# top_level.net
KiCad netlist of a schematic drawn in Altium Designer
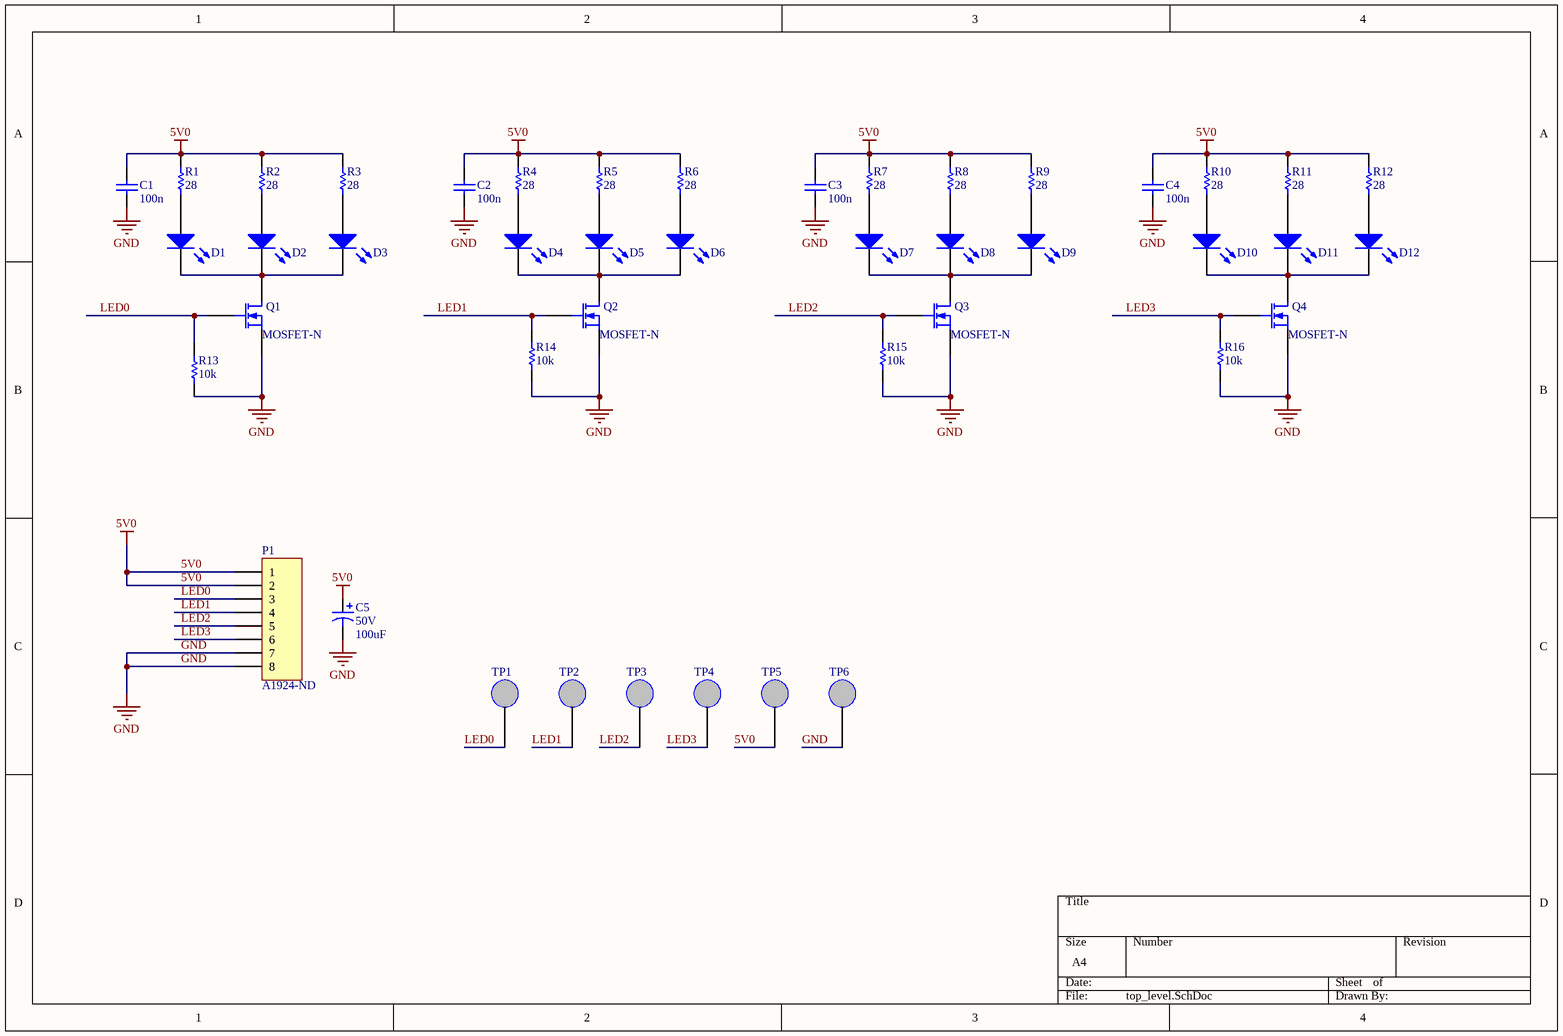
[diagram p0: top_level.SchDoc]

(export (version "E")
  (design (tool "Eeschema 10.0.6"))
  (components
    (comp (ref "C1")
      (value "100n")
      (footprint "CS-0603")
      (fields
        (field (name "TOLERANCE") "10%")
        (field (name "VOLTAGE") "16V")
        (field (name "Comment") "CS - CAPACITOR")
      )
      (libsource (lib "CHINOOK_LIBRARY") (part "CS - CAPACITOR"))
    )
    (comp (ref "C2")
      (value "100n")
      (footprint "CS-0603")
      (fields
        (field (name "TOLERANCE") "10%")
        (field (name "VOLTAGE") "16V")
        (field (name "Comment") "CS - CAPACITOR")
      )
      (libsource (lib "CHINOOK_LIBRARY") (part "CS - CAPACITOR"))
    )
    (comp (ref "C3")
      (value "100n")
      (footprint "CS-0603")
      (fields
        (field (name "TOLERANCE") "10%")
        (field (name "VOLTAGE") "16V")
        (field (name "Comment") "CS - CAPACITOR")
      )
      (libsource (lib "CHINOOK_LIBRARY") (part "CS - CAPACITOR"))
    )
    (comp (ref "C4")
      (value "100n")
      (footprint "CS-0603")
      (fields
        (field (name "TOLERANCE") "10%")
        (field (name "VOLTAGE") "16V")
        (field (name "Comment") "CS - CAPACITOR")
      )
      (libsource (lib "CHINOOK_LIBRARY") (part "CS - CAPACITOR"))
    )
    (comp (ref "C5")
      (value "100uF")
      (footprint "CT-CAP-ALUM-8X14")
      (fields
        (field (name "TOLERANCE") "10%")
        (field (name "VOLTAGE") "50V")
        (field (name "Comment") "CT - CAPACITOR ELECTROLYTIC")
      )
      (libsource (lib "CHINOOK_LIBRARY") (part "CT - CAPACITOR ELECTROLYTIC"))
    )
    (comp (ref "D1")
      (value "LED - NORMAL LED")
      (footprint "LED-1")
      (libsource (lib "CHINOOK_LIBRARY") (part "LED - NORMAL LED"))
    )
    (comp (ref "D2")
      (value "LED - NORMAL LED")
      (footprint "LED-1")
      (libsource (lib "CHINOOK_LIBRARY") (part "LED - NORMAL LED"))
    )
    (comp (ref "D3")
      (value "LED - NORMAL LED")
      (footprint "LED-1")
      (libsource (lib "CHINOOK_LIBRARY") (part "LED - NORMAL LED"))
    )
    (comp (ref "D4")
      (value "LED - NORMAL LED")
      (footprint "LED-1")
      (libsource (lib "CHINOOK_LIBRARY") (part "LED - NORMAL LED"))
    )
    (comp (ref "D5")
      (value "LED - NORMAL LED")
      (footprint "LED-1")
      (libsource (lib "CHINOOK_LIBRARY") (part "LED - NORMAL LED"))
    )
    (comp (ref "D6")
      (value "LED - NORMAL LED")
      (footprint "LED-1")
      (libsource (lib "CHINOOK_LIBRARY") (part "LED - NORMAL LED"))
    )
    (comp (ref "D7")
      (value "LED - NORMAL LED")
      (footprint "LED-1")
      (libsource (lib "CHINOOK_LIBRARY") (part "LED - NORMAL LED"))
    )
    (comp (ref "D8")
      (value "LED - NORMAL LED")
      (footprint "LED-1")
      (libsource (lib "CHINOOK_LIBRARY") (part "LED - NORMAL LED"))
    )
    (comp (ref "D9")
      (value "LED - NORMAL LED")
      (footprint "LED-1")
      (libsource (lib "CHINOOK_LIBRARY") (part "LED - NORMAL LED"))
    )
    (comp (ref "D10")
      (value "LED - NORMAL LED")
      (footprint "LED-1")
      (libsource (lib "CHINOOK_LIBRARY") (part "LED - NORMAL LED"))
    )
    (comp (ref "D11")
      (value "LED - NORMAL LED")
      (footprint "LED-1")
      (libsource (lib "CHINOOK_LIBRARY") (part "LED - NORMAL LED"))
    )
    (comp (ref "D12")
      (value "LED - NORMAL LED")
      (footprint "LED-1")
      (libsource (lib "CHINOOK_LIBRARY") (part "LED - NORMAL LED"))
    )
    (comp (ref "P1")
      (value "CON - HEADER 1X8")
      (footprint "CON-HEADER-1X8")
      (description "100mil header 1 row 6 pins")
      (fields (field (name "SUPPLIER PART NUMBER 1") "A1924-ND"))
      (libsource (lib "CHINOOK_LIBRARY") (part "CON - HEADER 1X8"))
    )
    (comp (ref "Q1")
      (value "MOSFET-N")
      (footprint "TO-220AB")
      (description "N-Channel MOSFET")
      (fields (field (name "PUBLISHER") "Altium Limited"))
      (libsource (lib "Miscellaneous Devices") (part "MOSFET-N"))
    )
    (comp (ref "Q2")
      (value "MOSFET-N")
      (footprint "TO-220AB")
      (description "N-Channel MOSFET")
      (fields (field (name "PUBLISHER") "Altium Limited"))
      (libsource (lib "Miscellaneous Devices") (part "MOSFET-N"))
    )
    (comp (ref "Q3")
      (value "MOSFET-N")
      (footprint "TO-220AB")
      (description "N-Channel MOSFET")
      (fields (field (name "PUBLISHER") "Altium Limited"))
      (libsource (lib "Miscellaneous Devices") (part "MOSFET-N"))
    )
    (comp (ref "Q4")
      (value "MOSFET-N")
      (footprint "TO-220AB")
      (description "N-Channel MOSFET")
      (fields (field (name "PUBLISHER") "Altium Limited"))
      (libsource (lib "Miscellaneous Devices") (part "MOSFET-N"))
    )
    (comp (ref "R1")
      (value "28")
      (footprint "RS-1210")
      (fields
        (field (name "TOLERANCE") "RES TOL")
        (field (name "POWER") "RES POWER")
        (field (name "Comment") "RS - RESISTOR")
      )
      (libsource (lib "CHINOOK_LIBRARY") (part "RS - RESISTOR"))
    )
    (comp (ref "R2")
      (value "28")
      (footprint "RS-1210")
      (fields
        (field (name "TOLERANCE") "RES TOL")
        (field (name "POWER") "RES POWER")
        (field (name "Comment") "RS - RESISTOR")
      )
      (libsource (lib "CHINOOK_LIBRARY") (part "RS - RESISTOR"))
    )
    (comp (ref "R3")
      (value "28")
      (footprint "RS-1210")
      (fields
        (field (name "TOLERANCE") "RES TOL")
        (field (name "POWER") "RES POWER")
        (field (name "Comment") "RS - RESISTOR")
      )
      (libsource (lib "CHINOOK_LIBRARY") (part "RS - RESISTOR"))
    )
    (comp (ref "R4")
      (value "28")
      (footprint "RS-1210")
      (fields
        (field (name "TOLERANCE") "RES TOL")
        (field (name "POWER") "RES POWER")
        (field (name "Comment") "RS - RESISTOR")
      )
      (libsource (lib "CHINOOK_LIBRARY") (part "RS - RESISTOR"))
    )
    (comp (ref "R5")
      (value "28")
      (footprint "RS-1210")
      (fields
        (field (name "TOLERANCE") "RES TOL")
        (field (name "POWER") "RES POWER")
        (field (name "Comment") "RS - RESISTOR")
      )
      (libsource (lib "CHINOOK_LIBRARY") (part "RS - RESISTOR"))
    )
    (comp (ref "R6")
      (value "28")
      (footprint "RS-1210")
      (fields
        (field (name "TOLERANCE") "RES TOL")
        (field (name "POWER") "RES POWER")
        (field (name "Comment") "RS - RESISTOR")
      )
      (libsource (lib "CHINOOK_LIBRARY") (part "RS - RESISTOR"))
    )
    (comp (ref "R7")
      (value "28")
      (footprint "RS-1210")
      (fields
        (field (name "TOLERANCE") "RES TOL")
        (field (name "POWER") "RES POWER")
        (field (name "Comment") "RS - RESISTOR")
      )
      (libsource (lib "CHINOOK_LIBRARY") (part "RS - RESISTOR"))
    )
    (comp (ref "R8")
      (value "28")
      (footprint "RS-1210")
      (fields
        (field (name "TOLERANCE") "RES TOL")
        (field (name "POWER") "RES POWER")
        (field (name "Comment") "RS - RESISTOR")
      )
      (libsource (lib "CHINOOK_LIBRARY") (part "RS - RESISTOR"))
    )
    (comp (ref "R9")
      (value "28")
      (footprint "RS-1210")
      (fields
        (field (name "TOLERANCE") "RES TOL")
        (field (name "POWER") "RES POWER")
        (field (name "Comment") "RS - RESISTOR")
      )
      (libsource (lib "CHINOOK_LIBRARY") (part "RS - RESISTOR"))
    )
    (comp (ref "R10")
      (value "28")
      (footprint "RS-1210")
      (fields
        (field (name "TOLERANCE") "RES TOL")
        (field (name "POWER") "RES POWER")
        (field (name "Comment") "RS - RESISTOR")
      )
      (libsource (lib "CHINOOK_LIBRARY") (part "RS - RESISTOR"))
    )
    (comp (ref "R11")
      (value "28")
      (footprint "RS-1210")
      (fields
        (field (name "TOLERANCE") "RES TOL")
        (field (name "POWER") "RES POWER")
        (field (name "Comment") "RS - RESISTOR")
      )
      (libsource (lib "CHINOOK_LIBRARY") (part "RS - RESISTOR"))
    )
    (comp (ref "R12")
      (value "28")
      (footprint "RS-1210")
      (fields
        (field (name "TOLERANCE") "RES TOL")
        (field (name "POWER") "RES POWER")
        (field (name "Comment") "RS - RESISTOR")
      )
      (libsource (lib "CHINOOK_LIBRARY") (part "RS - RESISTOR"))
    )
    (comp (ref "R13")
      (value "10k")
      (footprint "RS-0603")
      (fields
        (field (name "TOLERANCE") "RES TOL")
        (field (name "POWER") "RES POWER")
        (field (name "Comment") "RS - RESISTOR")
      )
      (libsource (lib "CHINOOK_LIBRARY") (part "RS - RESISTOR"))
    )
    (comp (ref "R14")
      (value "10k")
      (footprint "RS-0603")
      (fields
        (field (name "TOLERANCE") "RES TOL")
        (field (name "POWER") "RES POWER")
        (field (name "Comment") "RS - RESISTOR")
      )
      (libsource (lib "CHINOOK_LIBRARY") (part "RS - RESISTOR"))
    )
    (comp (ref "R15")
      (value "10k")
      (footprint "RS-0603")
      (fields
        (field (name "TOLERANCE") "RES TOL")
        (field (name "POWER") "RES POWER")
        (field (name "Comment") "RS - RESISTOR")
      )
      (libsource (lib "CHINOOK_LIBRARY") (part "RS - RESISTOR"))
    )
    (comp (ref "R16")
      (value "10k")
      (footprint "RS-0603")
      (fields
        (field (name "TOLERANCE") "RES TOL")
        (field (name "POWER") "RES POWER")
        (field (name "Comment") "RS - RESISTOR")
      )
      (libsource (lib "CHINOOK_LIBRARY") (part "RS - RESISTOR"))
    )
    (comp (ref "TP1")
      (value "5003K")
      (footprint "TP - VERTICAL")
      (libsource (lib "CHINOOK_LIBRARY") (part "TP - Test point vertical"))
    )
    (comp (ref "TP2")
      (value "5003K")
      (footprint "TP - VERTICAL")
      (libsource (lib "CHINOOK_LIBRARY") (part "TP - Test point vertical"))
    )
    (comp (ref "TP3")
      (value "5003K")
      (footprint "TP - VERTICAL")
      (libsource (lib "CHINOOK_LIBRARY") (part "TP - Test point vertical"))
    )
    (comp (ref "TP4")
      (value "5003K")
      (footprint "TP - VERTICAL")
      (libsource (lib "CHINOOK_LIBRARY") (part "TP - Test point vertical"))
    )
    (comp (ref "TP5")
      (value "5003K")
      (footprint "TP - VERTICAL")
      (libsource (lib "CHINOOK_LIBRARY") (part "TP - Test point vertical"))
    )
    (comp (ref "TP6")
      (value "5003K")
      (footprint "TP - VERTICAL")
      (libsource (lib "CHINOOK_LIBRARY") (part "TP - Test point vertical"))
    )
  )
  (nets
    (net (code "1") (name "/LED0") (class "Default")
      (node (ref "P1") (pin "3") (pinfunction "3_3") (pintype "passive"))
      (node (ref "Q1") (pin "2") (pinfunction "G_2") (pintype "passive"))
      (node (ref "R13") (pin "2") (pinfunction "2_2") (pintype "passive"))
      (node (ref "TP1") (pin "1") (pinfunction "1_1") (pintype "passive"))
    )
    (net (code "2") (name "/LED1") (class "Default")
      (node (ref "P1") (pin "4") (pinfunction "4_4") (pintype "passive"))
      (node (ref "Q2") (pin "2") (pinfunction "G_2") (pintype "passive"))
      (node (ref "R14") (pin "2") (pinfunction "2_2") (pintype "passive"))
      (node (ref "TP2") (pin "1") (pinfunction "1_1") (pintype "passive"))
    )
    (net (code "3") (name "/LED2") (class "Default")
      (node (ref "P1") (pin "5") (pinfunction "5_5") (pintype "passive"))
      (node (ref "Q3") (pin "2") (pinfunction "G_2") (pintype "passive"))
      (node (ref "R15") (pin "2") (pinfunction "2_2") (pintype "passive"))
      (node (ref "TP3") (pin "1") (pinfunction "1_1") (pintype "passive"))
    )
    (net (code "4") (name "/LED3") (class "Default")
      (node (ref "P1") (pin "6") (pinfunction "6_6") (pintype "passive"))
      (node (ref "Q4") (pin "2") (pinfunction "G_2") (pintype "passive"))
      (node (ref "R16") (pin "2") (pinfunction "2_2") (pintype "passive"))
      (node (ref "TP4") (pin "1") (pinfunction "1_1") (pintype "passive"))
    )
    (net (code "5") (name "5V0") (class "Default")
      (node (ref "C1") (pin "1") (pinfunction "1_1") (pintype "passive"))
      (node (ref "C2") (pin "1") (pinfunction "1_1") (pintype "passive"))
      (node (ref "C3") (pin "1") (pinfunction "1_1") (pintype "passive"))
      (node (ref "C4") (pin "1") (pinfunction "1_1") (pintype "passive"))
      (node (ref "C5") (pin "1") (pinfunction "1_1") (pintype "passive"))
      (node (ref "P1") (pin "1") (pinfunction "1_1") (pintype "passive"))
      (node (ref "P1") (pin "2") (pinfunction "2_2") (pintype "passive"))
      (node (ref "R1") (pin "2") (pinfunction "2_2") (pintype "passive"))
      (node (ref "R10") (pin "2") (pinfunction "2_2") (pintype "passive"))
      (node (ref "R11") (pin "2") (pinfunction "2_2") (pintype "passive"))
      (node (ref "R12") (pin "2") (pinfunction "2_2") (pintype "passive"))
      (node (ref "R2") (pin "2") (pinfunction "2_2") (pintype "passive"))
      (node (ref "R3") (pin "2") (pinfunction "2_2") (pintype "passive"))
      (node (ref "R4") (pin "2") (pinfunction "2_2") (pintype "passive"))
      (node (ref "R5") (pin "2") (pinfunction "2_2") (pintype "passive"))
      (node (ref "R6") (pin "2") (pinfunction "2_2") (pintype "passive"))
      (node (ref "R7") (pin "2") (pinfunction "2_2") (pintype "passive"))
      (node (ref "R8") (pin "2") (pinfunction "2_2") (pintype "passive"))
      (node (ref "R9") (pin "2") (pinfunction "2_2") (pintype "passive"))
      (node (ref "TP5") (pin "1") (pinfunction "1_1") (pintype "passive"))
    )
    (net (code "6") (name "GND") (class "Default")
      (node (ref "C1") (pin "2") (pinfunction "2_2") (pintype "passive"))
      (node (ref "C2") (pin "2") (pinfunction "2_2") (pintype "passive"))
      (node (ref "C3") (pin "2") (pinfunction "2_2") (pintype "passive"))
      (node (ref "C4") (pin "2") (pinfunction "2_2") (pintype "passive"))
      (node (ref "C5") (pin "2") (pinfunction "2_2") (pintype "passive"))
      (node (ref "P1") (pin "7") (pinfunction "7_7") (pintype "passive"))
      (node (ref "P1") (pin "8") (pinfunction "8_8") (pintype "passive"))
      (node (ref "Q1") (pin "3") (pinfunction "S_3") (pintype "passive"))
      (node (ref "Q2") (pin "3") (pinfunction "S_3") (pintype "passive"))
      (node (ref "Q3") (pin "3") (pinfunction "S_3") (pintype "passive"))
      (node (ref "Q4") (pin "3") (pinfunction "S_3") (pintype "passive"))
      (node (ref "R13") (pin "1") (pinfunction "1_1") (pintype "passive"))
      (node (ref "R14") (pin "1") (pinfunction "1_1") (pintype "passive"))
      (node (ref "R15") (pin "1") (pinfunction "1_1") (pintype "passive"))
      (node (ref "R16") (pin "1") (pinfunction "1_1") (pintype "passive"))
      (node (ref "TP6") (pin "1") (pinfunction "1_1") (pintype "passive"))
    )
    (net (code "7") (name "Net-(D1-PadA)") (class "Default")
      (node (ref "D1") (pin "A") (pinfunction "A_A") (pintype "passive"))
      (node (ref "R1") (pin "1") (pinfunction "1_1") (pintype "passive"))
    )
    (net (code "8") (name "Net-(D2-PadA)") (class "Default")
      (node (ref "D2") (pin "A") (pinfunction "A_A") (pintype "passive"))
      (node (ref "R2") (pin "1") (pinfunction "1_1") (pintype "passive"))
    )
    (net (code "9") (name "Net-(D3-PadA)") (class "Default")
      (node (ref "D3") (pin "A") (pinfunction "A_A") (pintype "passive"))
      (node (ref "R3") (pin "1") (pinfunction "1_1") (pintype "passive"))
    )
    (net (code "10") (name "Net-(D4-PadA)") (class "Default")
      (node (ref "D4") (pin "A") (pinfunction "A_A") (pintype "passive"))
      (node (ref "R4") (pin "1") (pinfunction "1_1") (pintype "passive"))
    )
    (net (code "11") (name "Net-(D5-PadA)") (class "Default")
      (node (ref "D5") (pin "A") (pinfunction "A_A") (pintype "passive"))
      (node (ref "R5") (pin "1") (pinfunction "1_1") (pintype "passive"))
    )
    (net (code "12") (name "Net-(D6-PadA)") (class "Default")
      (node (ref "D6") (pin "A") (pinfunction "A_A") (pintype "passive"))
      (node (ref "R6") (pin "1") (pinfunction "1_1") (pintype "passive"))
    )
    (net (code "13") (name "Net-(D7-PadA)") (class "Default")
      (node (ref "D7") (pin "A") (pinfunction "A_A") (pintype "passive"))
      (node (ref "R7") (pin "1") (pinfunction "1_1") (pintype "passive"))
    )
    (net (code "14") (name "Net-(D8-PadA)") (class "Default")
      (node (ref "D8") (pin "A") (pinfunction "A_A") (pintype "passive"))
      (node (ref "R8") (pin "1") (pinfunction "1_1") (pintype "passive"))
    )
    (net (code "15") (name "Net-(D9-PadA)") (class "Default")
      (node (ref "D9") (pin "A") (pinfunction "A_A") (pintype "passive"))
      (node (ref "R9") (pin "1") (pinfunction "1_1") (pintype "passive"))
    )
    (net (code "16") (name "Net-(D10-PadA)") (class "Default")
      (node (ref "D10") (pin "A") (pinfunction "A_A") (pintype "passive"))
      (node (ref "R10") (pin "1") (pinfunction "1_1") (pintype "passive"))
    )
    (net (code "17") (name "Net-(D11-PadA)") (class "Default")
      (node (ref "D11") (pin "A") (pinfunction "A_A") (pintype "passive"))
      (node (ref "R11") (pin "1") (pinfunction "1_1") (pintype "passive"))
    )
    (net (code "18") (name "Net-(D12-PadA)") (class "Default")
      (node (ref "D12") (pin "A") (pinfunction "A_A") (pintype "passive"))
      (node (ref "R12") (pin "1") (pinfunction "1_1") (pintype "passive"))
    )
    (net (code "19") (name "Net-(Q1-D)") (class "Default")
      (node (ref "D1") (pin "K") (pinfunction "K_K") (pintype "passive"))
      (node (ref "D2") (pin "K") (pinfunction "K_K") (pintype "passive"))
      (node (ref "D3") (pin "K") (pinfunction "K_K") (pintype "passive"))
      (node (ref "Q1") (pin "1") (pinfunction "D_1") (pintype "passive"))
    )
    (net (code "20") (name "Net-(Q2-D)") (class "Default")
      (node (ref "D4") (pin "K") (pinfunction "K_K") (pintype "passive"))
      (node (ref "D5") (pin "K") (pinfunction "K_K") (pintype "passive"))
      (node (ref "D6") (pin "K") (pinfunction "K_K") (pintype "passive"))
      (node (ref "Q2") (pin "1") (pinfunction "D_1") (pintype "passive"))
    )
    (net (code "21") (name "Net-(Q3-D)") (class "Default")
      (node (ref "D7") (pin "K") (pinfunction "K_K") (pintype "passive"))
      (node (ref "D8") (pin "K") (pinfunction "K_K") (pintype "passive"))
      (node (ref "D9") (pin "K") (pinfunction "K_K") (pintype "passive"))
      (node (ref "Q3") (pin "1") (pinfunction "D_1") (pintype "passive"))
    )
    (net (code "22") (name "Net-(Q4-D)") (class "Default")
      (node (ref "D10") (pin "K") (pinfunction "K_K") (pintype "passive"))
      (node (ref "D11") (pin "K") (pinfunction "K_K") (pintype "passive"))
      (node (ref "D12") (pin "K") (pinfunction "K_K") (pintype "passive"))
      (node (ref "Q4") (pin "1") (pinfunction "D_1") (pintype "passive"))
    )
  )
)
